# 07-multimodal-microcontroller.net
KiCad netlist of a schematic drawn in Altium Designer
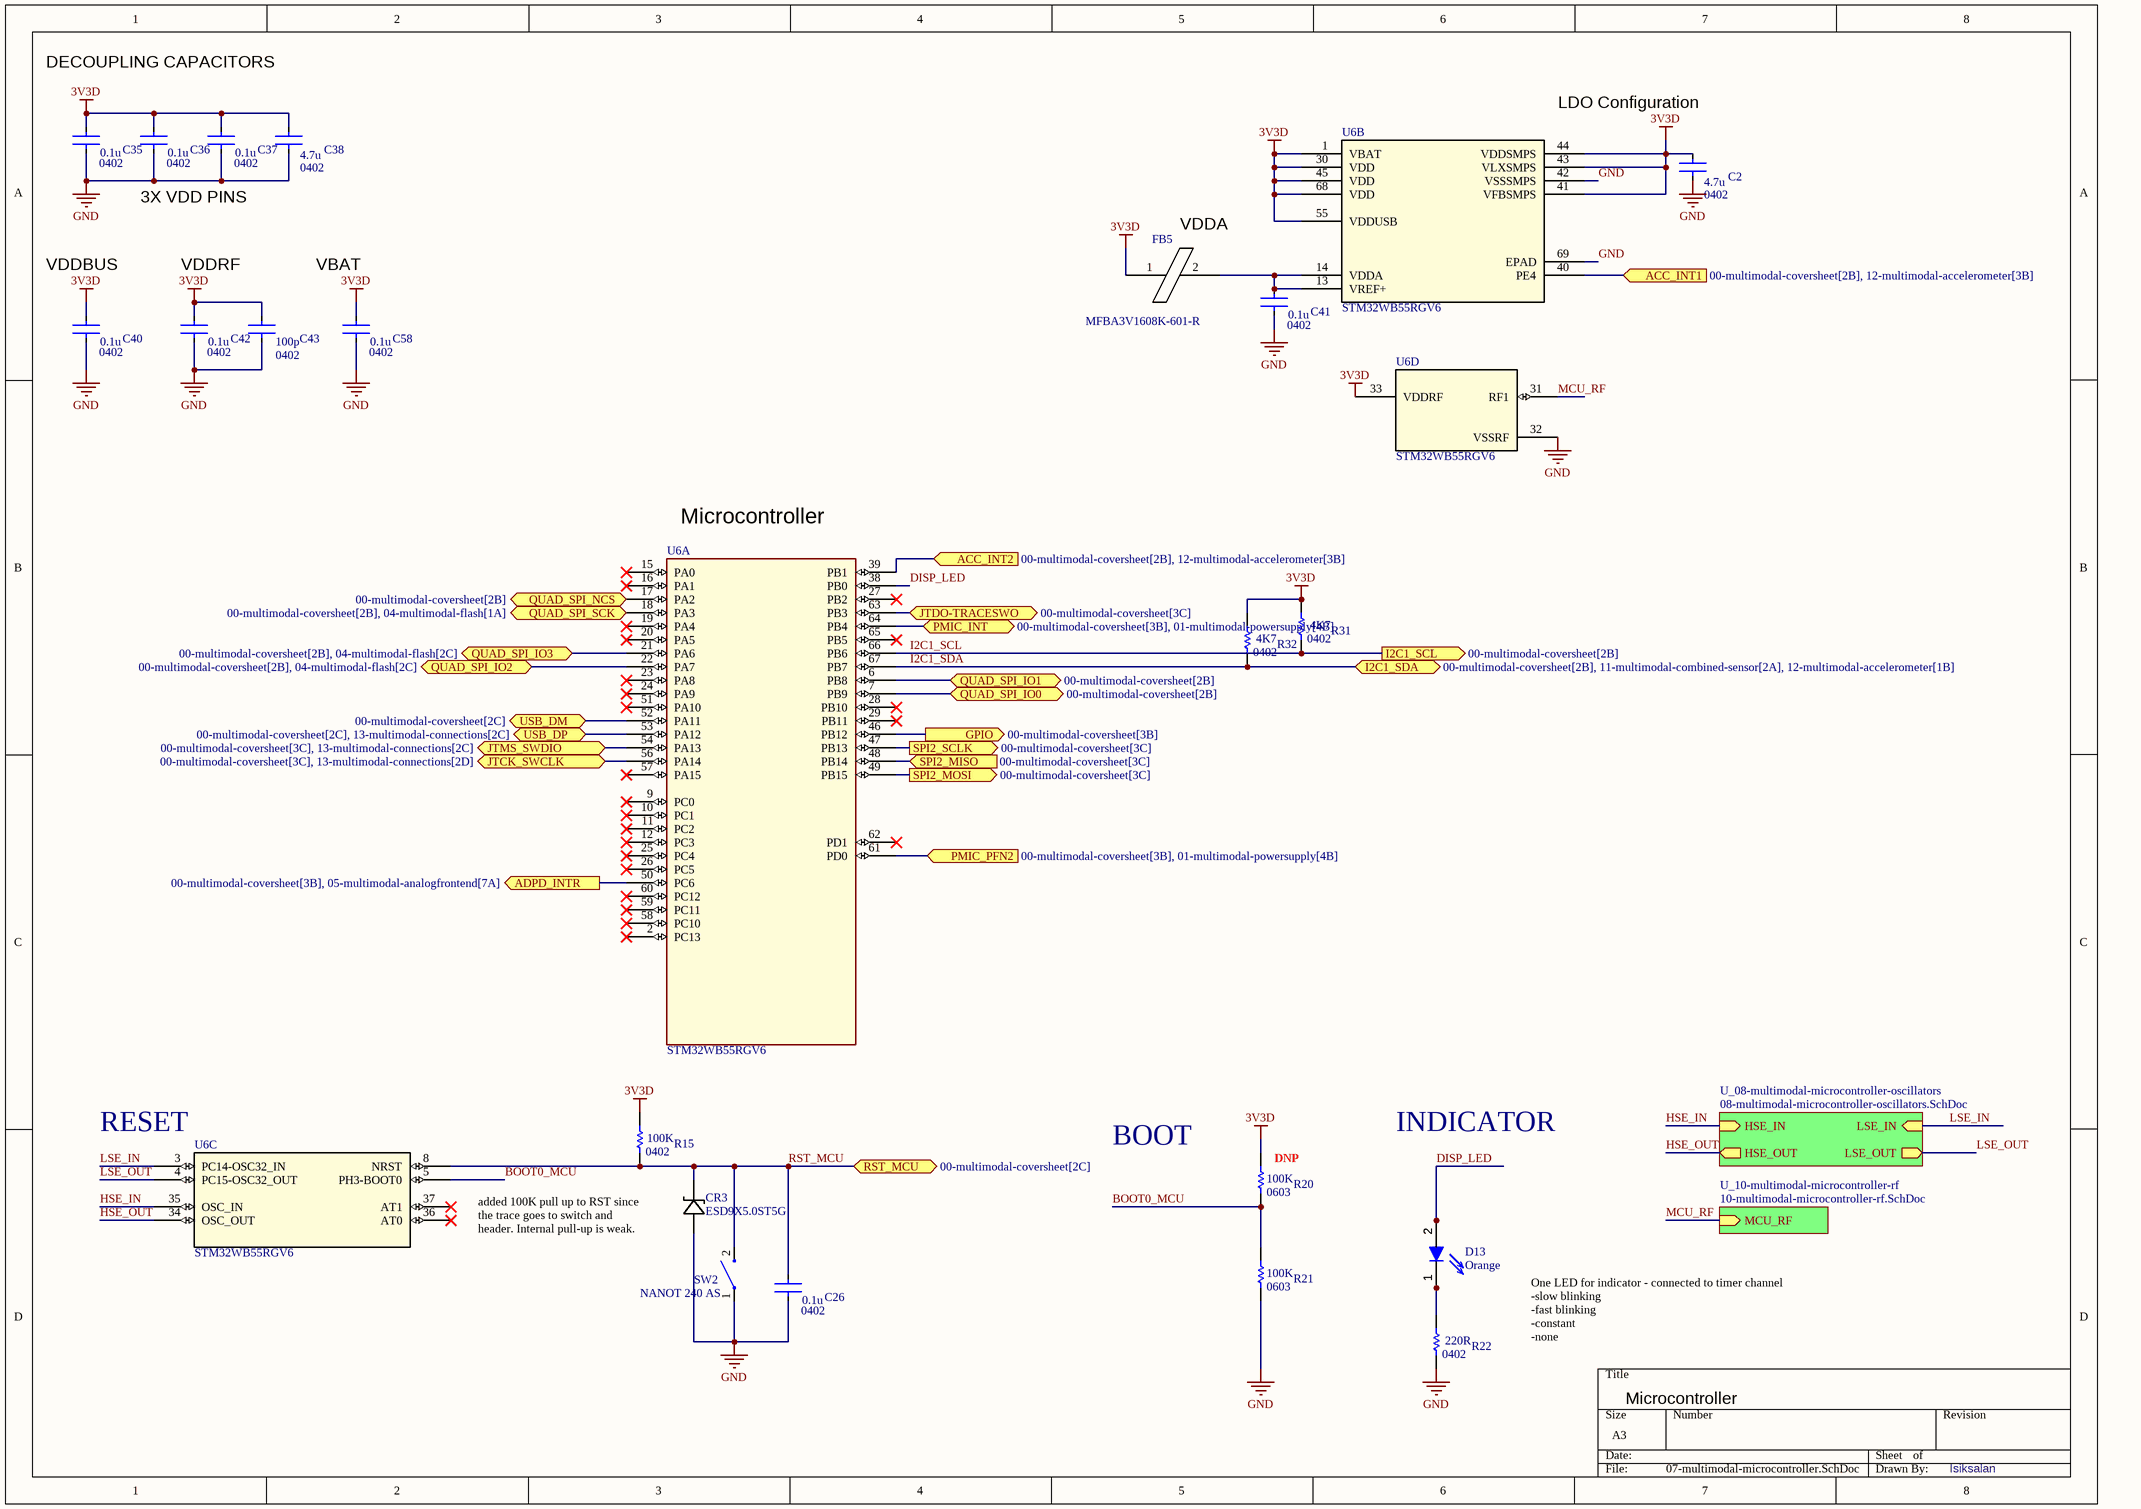
[diagram p0: 07-multimodal-microcontroller.SchDoc]

(export (version "E")
  (design (tool "Eeschema 10.0.6"))
  (components
    (comp (ref "C2")
      (value "C1005X5R1A475K050BC")
      (footprint "CAPTDK0402")
      (description "CAP CER 4.7UF 10V X5R 0402")
      (libsource (lib "multimodal") (part "C1005X5R1A475K050BC"))
    )
    (comp (ref "C26")
      (value "C1005X7R1H104K050BB")
      (footprint "CAPTDK0402")
      (description "CAP CER 0.1UF 50V X7R 0402")
      (libsource (lib "multimodal") (part "C1005X7R1H104K050BB"))
    )
    (comp (ref "C35")
      (value "C1005X7R1H104K050BB")
      (footprint "CAPTDK0402")
      (description "CAP CER 0.1UF 50V X7R 0402")
      (libsource (lib "multimodal") (part "C1005X7R1H104K050BB"))
    )
    (comp (ref "C36")
      (value "C1005X7R1H104K050BB")
      (footprint "CAPTDK0402")
      (description "CAP CER 0.1UF 50V X7R 0402")
      (libsource (lib "multimodal") (part "C1005X7R1H104K050BB"))
    )
    (comp (ref "C37")
      (value "C1005X7R1H104K050BB")
      (footprint "CAPTDK0402")
      (description "CAP CER 0.1UF 50V X7R 0402")
      (libsource (lib "multimodal") (part "C1005X7R1H104K050BB"))
    )
    (comp (ref "C38")
      (value "C1005X5R1A475K050BC")
      (footprint "CAPTDK0402")
      (description "CAP CER 4.7UF 10V X5R 0402")
      (libsource (lib "multimodal") (part "C1005X5R1A475K050BC"))
    )
    (comp (ref "C40")
      (value "C1005X7R1H104K050BB")
      (footprint "CAPTDK0402")
      (description "CAP CER 0.1UF 50V X7R 0402")
      (libsource (lib "multimodal") (part "C1005X7R1H104K050BB"))
    )
    (comp (ref "C41")
      (value "C1005X7R1H104K050BB")
      (footprint "CAPTDK0402")
      (description "CAP CER 0.1UF 50V X7R 0402")
      (libsource (lib "multimodal") (part "C1005X7R1H104K050BB"))
    )
    (comp (ref "C42")
      (value "C1005X7R1H104K050BB")
      (footprint "CAPTDK0402")
      (description "CAP CER 0.1UF 50V X7R 0402")
      (libsource (lib "multimodal") (part "C1005X7R1H104K050BB"))
    )
    (comp (ref "C43")
      (value "CGA2B2C0G1H101J050BA")
      (footprint "CAPTDK0402")
      (description "CAP CER 100PF 50V C0G 0402")
      (libsource (lib "multimodal") (part "CGA2B2C0G1H101J050BA_1"))
    )
    (comp (ref "C58")
      (value "C1005X7R1H104K050BB")
      (footprint "CAPTDK0402")
      (description "CAP CER 0.1UF 50V X7R 0402")
      (libsource (lib "multimodal") (part "C1005X7R1H104K050BB"))
    )
    (comp (ref "CR3")
      (value "ESD9X5.0ST5G")
      (footprint "SOD-923_514AB_ONS")
      (description "TVS DIODE 5VWM 12.3VC SOD923")
      (fields (field (name "COPYRIGHT") "Copyright (C) 2026 Ultra Librarian. All rights reserved."))
      (libsource (lib "multimodal") (part "ESD9X5.0ST5G"))
    )
    (comp (ref "D13")
      (value "Orange")
      (footprint "DISPLAY-LED")
      (description "LED ORANGE CLEAR 0603 SMD")
      (libsource (lib "multimodal") (part "LTST-C191KFKT"))
    )
    (comp (ref "FB5")
      (value "MFBA3V1608K-601-R")
      (footprint "INDMURT0603")
      (description "FERRITE BEAD 600 OHM 0603 1LN")
      (libsource (lib "multimodal") (part "MFBA3V1608K-601-R"))
    )
    (comp (ref "R15")
      (value "RMCF0402FT100K")
      (footprint "RES-STACK-POLE-0402")
      (description "RES 100K OHM 1% 1/16W 0402")
      (libsource (lib "multimodal") (part "RMCF0402FT100K"))
    )
    (comp (ref "R20")
      (value "RMCF0603JG100K")
      (footprint "RES-STACK-POLE-0603")
      (description "RES 100K OHM 5% 1/10W 0603")
      (libsource (lib "multimodal") (part "RMCF0603JG100K"))
    )
    (comp (ref "R21")
      (value "RMCF0603JG100K")
      (footprint "RES-STACK-POLE-0603")
      (description "RES 100K OHM 5% 1/10W 0603")
      (libsource (lib "multimodal") (part "RMCF0603JG100K"))
    )
    (comp (ref "R22")
      (value "RMCF0402JT220R")
      (footprint "RES-STACK-POLE-0402")
      (description "RES 220 OHM 5% 1/16W 0402")
      (libsource (lib "multimodal") (part "RMCF0402JT220R"))
    )
    (comp (ref "R31")
      (value "RMCF0402FT4K70")
      (footprint "RES-STACK-POLE-0402")
      (description "RES 4.7K OHM 1% 1/16W 0402")
      (libsource (lib "multimodal") (part "RMCF0402FT4K70"))
    )
    (comp (ref "R32")
      (value "RMCF0402FT4K70")
      (footprint "RES-STACK-POLE-0402")
      (description "RES 4.7K OHM 1% 1/16W 0402")
      (libsource (lib "multimodal") (part "RMCF0402FT4K70"))
    )
    (comp (ref "SW2")
      (value "NANOT 240 AS")
      (footprint "TACTILE-SWITCH - TINY")
      (description "SWITCH TACTILE SPST-NO 0.02A 15V")
      (libsource (lib "multimodal") (part "NANOT 240 AS"))
    )
    (comp (ref "U6")
      (value "STM32WB55RGV6")
      (footprint "STM32WB55RG")
      (fields (field (name "COPYRIGHT") "Copyright (C) 2025 Ultra Librarian. All rights reserved."))
      (libsource (lib "multimodal") (part "STM32WB55RGV6"))
    )
  )
  (nets
    (net (code "1") (name "/ACC_INT1") (class "Default")
      (node (ref "U6") (pin "40") (pinfunction "PE4_40") (pintype "power_in"))
    )
    (net (code "2") (name "/ACC_INT2") (class "Default")
      (node (ref "U6") (pin "39") (pinfunction "PB1_39") (pintype "bidirectional"))
    )
    (net (code "3") (name "/ADPD_INTR") (class "Default")
      (node (ref "U6") (pin "50") (pinfunction "PC6_50") (pintype "bidirectional"))
    )
    (net (code "4") (name "/BOOT0_MCU") (class "Default")
      (node (ref "R20") (pin "1") (pinfunction "1_1") (pintype "passive"))
      (node (ref "R21") (pin "2") (pinfunction "2_2") (pintype "passive"))
      (node (ref "U6") (pin "5") (pinfunction "PH3-BOOT0_5") (pintype "bidirectional"))
    )
    (net (code "5") (name "/DISP_LED") (class "Default")
      (node (ref "D13") (pin "2") (pintype "passive"))
      (node (ref "U6") (pin "38") (pinfunction "PB0_38") (pintype "bidirectional"))
    )
    (net (code "6") (name "/GPIO") (class "Default")
      (node (ref "U6") (pin "46") (pinfunction "PB12_46") (pintype "bidirectional"))
    )
    (net (code "7") (name "/HSE_IN") (class "Default")
      (node (ref "U6") (pin "35") (pinfunction "OSC_IN_35") (pintype "bidirectional"))
    )
    (net (code "8") (name "/HSE_OUT") (class "Default")
      (node (ref "U6") (pin "34") (pinfunction "OSC_OUT_34") (pintype "bidirectional"))
    )
    (net (code "9") (name "/I2C1_SCL") (class "Default")
      (node (ref "R31") (pin "1") (pinfunction "1_1") (pintype "passive"))
      (node (ref "U6") (pin "66") (pinfunction "PB6_66") (pintype "bidirectional"))
    )
    (net (code "10") (name "/I2C1_SDA") (class "Default")
      (node (ref "R32") (pin "1") (pinfunction "1_1") (pintype "passive"))
      (node (ref "U6") (pin "67") (pinfunction "PB7_67") (pintype "bidirectional"))
    )
    (net (code "11") (name "/JTCK_SWCLK") (class "Default")
      (node (ref "U6") (pin "56") (pinfunction "PA14_56") (pintype "bidirectional"))
    )
    (net (code "12") (name "/JTDO-TRACESWO") (class "Default")
      (node (ref "U6") (pin "63") (pinfunction "PB3_63") (pintype "bidirectional"))
    )
    (net (code "13") (name "/JTMS_SWDIO") (class "Default")
      (node (ref "U6") (pin "54") (pinfunction "PA13_54") (pintype "bidirectional"))
    )
    (net (code "14") (name "/LSE_IN") (class "Default")
      (node (ref "U6") (pin "3") (pinfunction "PC14-OSC32_IN_3") (pintype "bidirectional"))
    )
    (net (code "15") (name "/LSE_OUT") (class "Default")
      (node (ref "U6") (pin "4") (pinfunction "PC15-OSC32_OUT_4") (pintype "bidirectional"))
    )
    (net (code "16") (name "/MCU_RF") (class "Default")
      (node (ref "U6") (pin "31") (pinfunction "RF1_31") (pintype "bidirectional"))
    )
    (net (code "17") (name "/PMIC_INT") (class "Default")
      (node (ref "U6") (pin "64") (pinfunction "PB4_64") (pintype "bidirectional"))
    )
    (net (code "18") (name "/PMIC_PFN2") (class "Default")
      (node (ref "U6") (pin "61") (pinfunction "PD0_61") (pintype "bidirectional"))
    )
    (net (code "19") (name "/QUAD_SPI_IO0") (class "Default")
      (node (ref "U6") (pin "7") (pinfunction "PB9_7") (pintype "bidirectional"))
    )
    (net (code "20") (name "/QUAD_SPI_IO1") (class "Default")
      (node (ref "U6") (pin "6") (pinfunction "PB8_6") (pintype "bidirectional"))
    )
    (net (code "21") (name "/QUAD_SPI_IO2") (class "Default")
      (node (ref "U6") (pin "22") (pinfunction "PA7_22") (pintype "bidirectional"))
    )
    (net (code "22") (name "/QUAD_SPI_IO3") (class "Default")
      (node (ref "U6") (pin "21") (pinfunction "PA6_21") (pintype "bidirectional"))
    )
    (net (code "23") (name "/QUAD_SPI_NCS") (class "Default")
      (node (ref "U6") (pin "17") (pinfunction "PA2_17") (pintype "bidirectional"))
    )
    (net (code "24") (name "/QUAD_SPI_SCK") (class "Default")
      (node (ref "U6") (pin "18") (pinfunction "PA3_18") (pintype "bidirectional"))
    )
    (net (code "25") (name "/RST_MCU") (class "Default")
      (node (ref "C26") (pin "1") (pinfunction "1_1") (pintype "passive"))
      (node (ref "CR3") (pin "1") (pinfunction "1_1") (pintype "passive"))
      (node (ref "R15") (pin "1") (pinfunction "1_1") (pintype "passive"))
      (node (ref "SW2") (pin "2") (pinfunction "2_2") (pintype "passive"))
      (node (ref "U6") (pin "8") (pinfunction "NRST_8") (pintype "bidirectional"))
    )
    (net (code "26") (name "/SPI2_MISO") (class "Default")
      (node (ref "U6") (pin "48") (pinfunction "PB14_48") (pintype "bidirectional"))
    )
    (net (code "27") (name "/SPI2_MOSI") (class "Default")
      (node (ref "U6") (pin "49") (pinfunction "PB15_49") (pintype "bidirectional"))
    )
    (net (code "28") (name "/SPI2_SCLK") (class "Default")
      (node (ref "U6") (pin "47") (pinfunction "PB13_47") (pintype "bidirectional"))
    )
    (net (code "29") (name "/USB_DM") (class "Default")
      (node (ref "U6") (pin "52") (pinfunction "PA11_52") (pintype "bidirectional"))
    )
    (net (code "30") (name "/USB_DP") (class "Default")
      (node (ref "U6") (pin "53") (pinfunction "PA12_53") (pintype "bidirectional"))
    )
    (net (code "31") (name "3V3D") (class "Default")
      (node (ref "C2") (pin "1") (pinfunction "1_1") (pintype "passive"))
      (node (ref "C35") (pin "1") (pinfunction "1_1") (pintype "passive"))
      (node (ref "C36") (pin "1") (pinfunction "1_1") (pintype "passive"))
      (node (ref "C37") (pin "1") (pinfunction "1_1") (pintype "passive"))
      (node (ref "C38") (pin "1") (pinfunction "1_1") (pintype "passive"))
      (node (ref "C40") (pin "1") (pinfunction "1_1") (pintype "passive"))
      (node (ref "C42") (pin "1") (pinfunction "1_1") (pintype "passive"))
      (node (ref "C43") (pin "1") (pinfunction "1_1") (pintype "passive"))
      (node (ref "C58") (pin "1") (pinfunction "1_1") (pintype "passive"))
      (node (ref "FB5") (pin "1") (pinfunction "1_1") (pintype "passive"))
      (node (ref "R15") (pin "2") (pinfunction "2_2") (pintype "passive"))
      (node (ref "R20") (pin "2") (pinfunction "2_2") (pintype "passive"))
      (node (ref "R31") (pin "2") (pinfunction "2_2") (pintype "passive"))
      (node (ref "R32") (pin "2") (pinfunction "2_2") (pintype "passive"))
      (node (ref "U6") (pin "1") (pinfunction "VBAT_1") (pintype "power_in"))
      (node (ref "U6") (pin "30") (pinfunction "VDD_30") (pintype "power_in"))
      (node (ref "U6") (pin "33") (pinfunction "VDDRF_33") (pintype "power_in"))
      (node (ref "U6") (pin "41") (pinfunction "VFBSMPS_41") (pintype "power_in"))
      (node (ref "U6") (pin "43") (pinfunction "VLXSMPS_43") (pintype "power_in"))
      (node (ref "U6") (pin "44") (pinfunction "VDDSMPS_44") (pintype "power_in"))
      (node (ref "U6") (pin "45") (pinfunction "VDD_45") (pintype "power_in"))
      (node (ref "U6") (pin "55") (pinfunction "VDDUSB_55") (pintype "power_in"))
      (node (ref "U6") (pin "68") (pinfunction "VDD_68") (pintype "power_in"))
    )
    (net (code "32") (name "GND") (class "Default")
      (node (ref "C2") (pin "2") (pinfunction "2_2") (pintype "passive"))
      (node (ref "C26") (pin "2") (pinfunction "2_2") (pintype "passive"))
      (node (ref "C35") (pin "2") (pinfunction "2_2") (pintype "passive"))
      (node (ref "C36") (pin "2") (pinfunction "2_2") (pintype "passive"))
      (node (ref "C37") (pin "2") (pinfunction "2_2") (pintype "passive"))
      (node (ref "C38") (pin "2") (pinfunction "2_2") (pintype "passive"))
      (node (ref "C40") (pin "2") (pinfunction "2_2") (pintype "passive"))
      (node (ref "C41") (pin "2") (pinfunction "2_2") (pintype "passive"))
      (node (ref "C42") (pin "2") (pinfunction "2_2") (pintype "passive"))
      (node (ref "C43") (pin "2") (pinfunction "2_2") (pintype "passive"))
      (node (ref "C58") (pin "2") (pinfunction "2_2") (pintype "passive"))
      (node (ref "CR3") (pin "2") (pinfunction "2_2") (pintype "passive"))
      (node (ref "R21") (pin "1") (pinfunction "1_1") (pintype "passive"))
      (node (ref "R22") (pin "1") (pinfunction "1_1") (pintype "passive"))
      (node (ref "SW2") (pin "1") (pinfunction "1_1") (pintype "passive"))
      (node (ref "U6") (pin "32") (pinfunction "VSSRF_32") (pintype "power_in"))
      (node (ref "U6") (pin "42") (pinfunction "VSSSMPS_42") (pintype "power_in"))
      (node (ref "U6") (pin "69") (pinfunction "EPAD_69") (pintype "power_in"))
    )
    (net (code "33") (name "Net-(D13-Pad1)") (class "Default")
      (node (ref "D13") (pin "1") (pintype "passive"))
      (node (ref "R22") (pin "2") (pinfunction "2_2") (pintype "passive"))
    )
    (net (code "34") (name "Net-(U6B-VDDA)") (class "Default")
      (node (ref "C41") (pin "1") (pinfunction "1_1") (pintype "passive"))
      (node (ref "FB5") (pin "2") (pinfunction "2_2") (pintype "passive"))
      (node (ref "U6") (pin "13") (pinfunction "VREF+_13") (pintype "power_in"))
      (node (ref "U6") (pin "14") (pinfunction "VDDA_14") (pintype "power_in"))
    )
    (net (code "35") (name "unconnected-(U6A-PA0-Pad15)") (class "Default")
      (node (ref "U6") (pin "15") (pinfunction "PA0_15") (pintype "bidirectional+no_connect"))
    )
    (net (code "36") (name "unconnected-(U6A-PA1-Pad16)") (class "Default")
      (node (ref "U6") (pin "16") (pinfunction "PA1_16") (pintype "bidirectional+no_connect"))
    )
    (net (code "37") (name "unconnected-(U6A-PA4-Pad19)") (class "Default")
      (node (ref "U6") (pin "19") (pinfunction "PA4_19") (pintype "bidirectional+no_connect"))
    )
    (net (code "38") (name "unconnected-(U6A-PA5-Pad20)") (class "Default")
      (node (ref "U6") (pin "20") (pinfunction "PA5_20") (pintype "bidirectional+no_connect"))
    )
    (net (code "39") (name "unconnected-(U6A-PA8-Pad23)") (class "Default")
      (node (ref "U6") (pin "23") (pinfunction "PA8_23") (pintype "bidirectional+no_connect"))
    )
    (net (code "40") (name "unconnected-(U6A-PA9-Pad24)") (class "Default")
      (node (ref "U6") (pin "24") (pinfunction "PA9_24") (pintype "bidirectional+no_connect"))
    )
    (net (code "41") (name "unconnected-(U6A-PA10-Pad51)") (class "Default")
      (node (ref "U6") (pin "51") (pinfunction "PA10_51") (pintype "bidirectional+no_connect"))
    )
    (net (code "42") (name "unconnected-(U6A-PA15-Pad57)") (class "Default")
      (node (ref "U6") (pin "57") (pinfunction "PA15_57") (pintype "bidirectional+no_connect"))
    )
    (net (code "43") (name "unconnected-(U6A-PB2-Pad27)") (class "Default")
      (node (ref "U6") (pin "27") (pinfunction "PB2_27") (pintype "bidirectional+no_connect"))
    )
    (net (code "44") (name "unconnected-(U6A-PB5-Pad65)") (class "Default")
      (node (ref "U6") (pin "65") (pinfunction "PB5_65") (pintype "bidirectional+no_connect"))
    )
    (net (code "45") (name "unconnected-(U6A-PB10-Pad28)") (class "Default")
      (node (ref "U6") (pin "28") (pinfunction "PB10_28") (pintype "bidirectional+no_connect"))
    )
    (net (code "46") (name "unconnected-(U6A-PB11-Pad29)") (class "Default")
      (node (ref "U6") (pin "29") (pinfunction "PB11_29") (pintype "bidirectional+no_connect"))
    )
    (net (code "47") (name "unconnected-(U6A-PC0-Pad9)") (class "Default")
      (node (ref "U6") (pin "9") (pinfunction "PC0_9") (pintype "bidirectional+no_connect"))
    )
    (net (code "48") (name "unconnected-(U6A-PC1-Pad10)") (class "Default")
      (node (ref "U6") (pin "10") (pinfunction "PC1_10") (pintype "bidirectional+no_connect"))
    )
    (net (code "49") (name "unconnected-(U6A-PC2-Pad11)") (class "Default")
      (node (ref "U6") (pin "11") (pinfunction "PC2_11") (pintype "bidirectional+no_connect"))
    )
    (net (code "50") (name "unconnected-(U6A-PC3-Pad12)") (class "Default")
      (node (ref "U6") (pin "12") (pinfunction "PC3_12") (pintype "bidirectional+no_connect"))
    )
    (net (code "51") (name "unconnected-(U6A-PC4-Pad25)") (class "Default")
      (node (ref "U6") (pin "25") (pinfunction "PC4_25") (pintype "bidirectional+no_connect"))
    )
    (net (code "52") (name "unconnected-(U6A-PC5-Pad26)") (class "Default")
      (node (ref "U6") (pin "26") (pinfunction "PC5_26") (pintype "bidirectional+no_connect"))
    )
    (net (code "53") (name "unconnected-(U6A-PC10-Pad58)") (class "Default")
      (node (ref "U6") (pin "58") (pinfunction "PC10_58") (pintype "bidirectional+no_connect"))
    )
    (net (code "54") (name "unconnected-(U6A-PC11-Pad59)") (class "Default")
      (node (ref "U6") (pin "59") (pinfunction "PC11_59") (pintype "bidirectional+no_connect"))
    )
    (net (code "55") (name "unconnected-(U6A-PC12-Pad60)") (class "Default")
      (node (ref "U6") (pin "60") (pinfunction "PC12_60") (pintype "bidirectional+no_connect"))
    )
    (net (code "56") (name "unconnected-(U6A-PC13-Pad2)") (class "Default")
      (node (ref "U6") (pin "2") (pinfunction "PC13_2") (pintype "bidirectional+no_connect"))
    )
    (net (code "57") (name "unconnected-(U6A-PD1-Pad62)") (class "Default")
      (node (ref "U6") (pin "62") (pinfunction "PD1_62") (pintype "bidirectional+no_connect"))
    )
    (net (code "58") (name "unconnected-(U6C-AT0-Pad36)") (class "Default")
      (node (ref "U6") (pin "36") (pinfunction "AT0_36") (pintype "bidirectional+no_connect"))
    )
    (net (code "59") (name "unconnected-(U6C-AT1-Pad37)") (class "Default")
      (node (ref "U6") (pin "37") (pinfunction "AT1_37") (pintype "bidirectional+no_connect"))
    )
  )
)
